# M_J_ext_e_ink_disp-inv.net
KiCad netlist of a schematic drawn in EAGLE
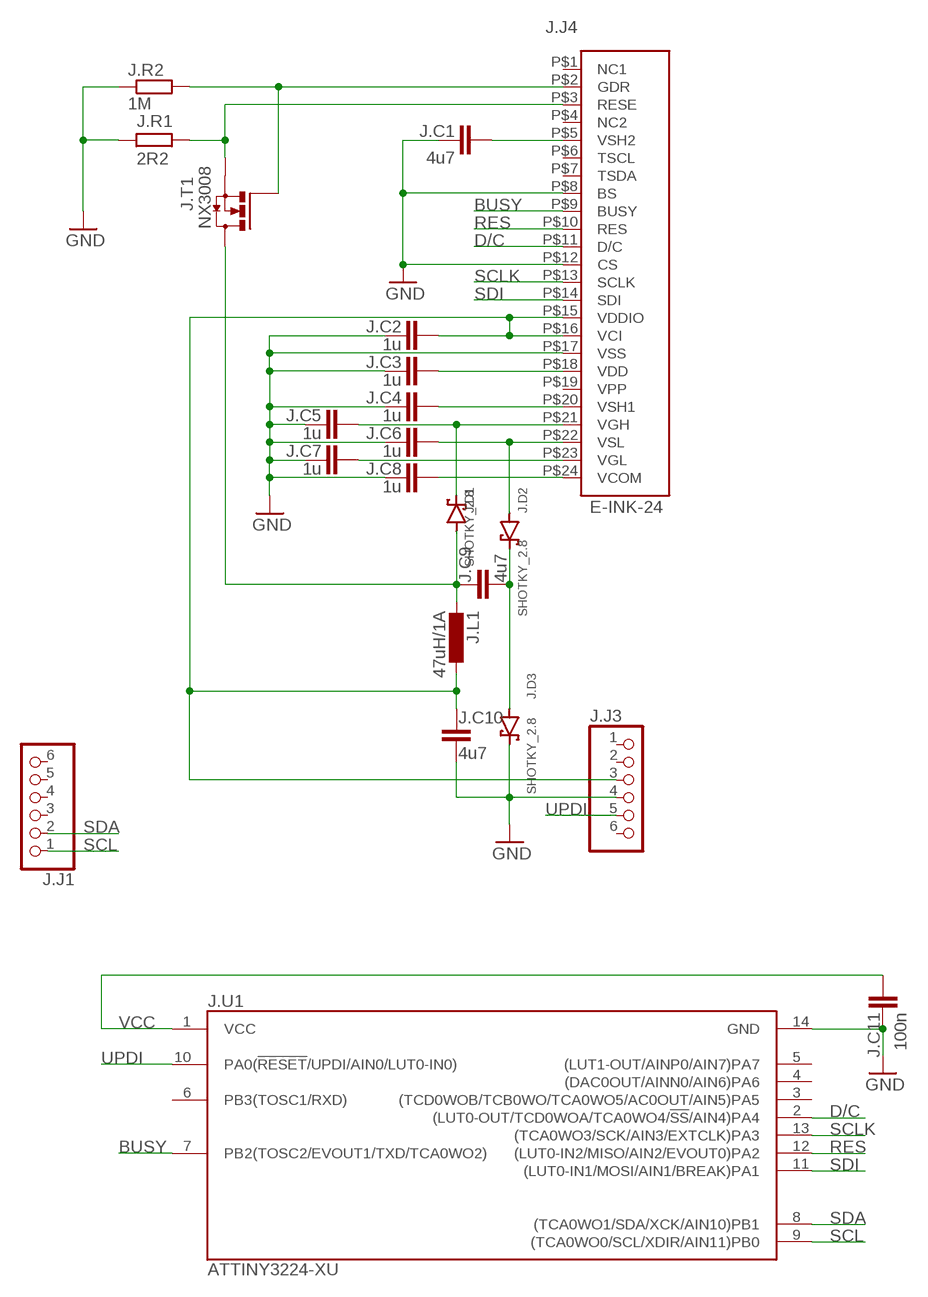
[diagram p0: schematic, sheet 1]

(export (version "E")
  (design (tool "Eeschema 10.0.6"))
  (components
    (comp (ref "J.C1")
      (value "4u7")
      (footprint "eagle-import:C0603")
      (libsource (lib "eagle-import") (part "C-EUC0603"))
    )
    (comp (ref "J.C2")
      (value "1u")
      (footprint "eagle-import:C0603")
      (libsource (lib "eagle-import") (part "C-EUC0603"))
    )
    (comp (ref "J.C3")
      (value "1u")
      (footprint "eagle-import:C0603")
      (libsource (lib "eagle-import") (part "C-EUC0603"))
    )
    (comp (ref "J.C4")
      (value "1u")
      (footprint "eagle-import:C0603")
      (libsource (lib "eagle-import") (part "C-EUC0603"))
    )
    (comp (ref "J.C5")
      (value "1u")
      (footprint "eagle-import:C0603")
      (libsource (lib "eagle-import") (part "C-EUC0603"))
    )
    (comp (ref "J.C6")
      (value "1u")
      (footprint "eagle-import:C0603")
      (libsource (lib "eagle-import") (part "C-EUC0603"))
    )
    (comp (ref "J.C7")
      (value "1u")
      (footprint "eagle-import:C0603")
      (libsource (lib "eagle-import") (part "C-EUC0603"))
    )
    (comp (ref "J.C8")
      (value "1u")
      (footprint "eagle-import:C0603")
      (libsource (lib "eagle-import") (part "C-EUC0603"))
    )
    (comp (ref "J.C9")
      (value "4u7")
      (footprint "eagle-import:C0603")
      (libsource (lib "eagle-import") (part "C-EUC0603"))
    )
    (comp (ref "J.C10")
      (value "4u7")
      (footprint "eagle-import:C0603")
      (libsource (lib "eagle-import") (part "C-EUC0603"))
    )
    (comp (ref "J.C11")
      (value "100n")
      (footprint "eagle-import:C0603")
      (libsource (lib "eagle-import") (part "C-EUC0603"))
    )
    (comp (ref "J.D1")
      (value "SHOTKY_2.8")
      (footprint "eagle-import:SHOTKY_2.8")
      (libsource (lib "eagle-import") (part "SHOTKY_2.8"))
    )
    (comp (ref "J.D2")
      (value "SHOTKY_2.8")
      (footprint "eagle-import:SHOTKY_2.8")
      (libsource (lib "eagle-import") (part "SHOTKY_2.8"))
    )
    (comp (ref "J.D3")
      (value "SHOTKY_2.8")
      (footprint "eagle-import:SHOTKY_2.8")
      (libsource (lib "eagle-import") (part "SHOTKY_2.8"))
    )
    (comp (ref "J.J1")
      (value "PINHD-1X6")
      (footprint "eagle-import:1X06")
      (libsource (lib "eagle-import") (part "PINHD-1X6"))
    )
    (comp (ref "J.J3")
      (value "PINHD-1X6")
      (footprint "eagle-import:1X06")
      (libsource (lib "eagle-import") (part "PINHD-1X6"))
    )
    (comp (ref "J.J4")
      (value "E-INK-24")
      (footprint "eagle-import:E-INK-24")
      (libsource (lib "eagle-import") (part "E-INK-24"))
    )
    (comp (ref "J.L1")
      (value "47uH/1A")
      (footprint "eagle-import:L3230M")
      (libsource (lib "eagle-import") (part "L-EUL3230M"))
    )
    (comp (ref "J.R1")
      (value "2R2")
      (footprint "eagle-import:R0603")
      (libsource (lib "eagle-import") (part "resistor_R-EU_R0603"))
    )
    (comp (ref "J.R2")
      (value "1M")
      (footprint "eagle-import:R0603")
      (libsource (lib "eagle-import") (part "R-EU_R0603"))
    )
    (comp (ref "J.T1")
      (value "NX3008")
      (footprint "eagle-import:SO23")
      (libsource (lib "eagle-import") (part "N-MOSFET"))
    )
    (comp (ref "J.U1")
      (value "ATTINY3224-XU")
      (footprint "eagle-import:TSSOP14")
      (libsource (lib "eagle-import") (part "ATTINY3224-XU"))
    )
  )
  (nets
    (net (code "1") (name "/BUSY") (class "Default")
      (node (ref "J.J4") (pin "P$9") (pinfunction "BUSY_P$9") (pintype "bidirectional"))
      (node (ref "J.U1") (pin "7") (pinfunction "PB2(TOSC2/EVOUT1/TXD/TCA0WO2)_7") (pintype "bidirectional"))
    )
    (net (code "2") (name "/D{slash}C") (class "Default")
      (node (ref "J.J4") (pin "P$11") (pinfunction "D/C_P$11") (pintype "bidirectional"))
      (node (ref "J.U1") (pin "2") (pinfunction "(LUT0-OUT/TCD0WOA/TCA0WO4/~{SS}/AIN4)PA4_2") (pintype "bidirectional"))
    )
    (net (code "3") (name "/RES") (class "Default")
      (node (ref "J.J4") (pin "P$10") (pinfunction "RES_P$10") (pintype "bidirectional"))
      (node (ref "J.U1") (pin "12") (pinfunction "(LUT0-IN2/MISO/AIN2/EVOUT0)PA2_12") (pintype "bidirectional"))
    )
    (net (code "4") (name "/SCL") (class "Default")
      (node (ref "J.J1") (pin "1") (pinfunction "1_1") (pintype "passive"))
      (node (ref "J.U1") (pin "9") (pinfunction "(TCA0WO0/SCL/XDIR/AIN11)PB0_9") (pintype "bidirectional"))
    )
    (net (code "5") (name "/SCLK") (class "Default")
      (node (ref "J.J4") (pin "P$13") (pinfunction "SCLK_P$13") (pintype "bidirectional"))
      (node (ref "J.U1") (pin "13") (pinfunction "(TCA0WO3/SCK/AIN3/EXTCLK)PA3_13") (pintype "bidirectional"))
    )
    (net (code "6") (name "/SDA") (class "Default")
      (node (ref "J.J1") (pin "2") (pinfunction "2_2") (pintype "passive"))
      (node (ref "J.U1") (pin "8") (pinfunction "(TCA0WO1/SDA/XCK/AIN10)PB1_8") (pintype "bidirectional"))
    )
    (net (code "7") (name "/SDI") (class "Default")
      (node (ref "J.J4") (pin "P$14") (pinfunction "SDI_P$14") (pintype "bidirectional"))
      (node (ref "J.U1") (pin "11") (pinfunction "(LUT0-IN1/MOSI/AIN1/BREAK)PA1_11") (pintype "bidirectional"))
    )
    (net (code "8") (name "/UPDI") (class "Default")
      (node (ref "J.J3") (pin "5") (pinfunction "5_5") (pintype "passive"))
      (node (ref "J.U1") (pin "10") (pinfunction "PA0(~{RESET}/UPDI/AIN0/LUT0-IN0)_10") (pintype "bidirectional"))
    )
    (net (code "9") (name "/VCC") (class "Default")
      (node (ref "J.C10") (pin "1") (pinfunction "1_1") (pintype "passive"))
      (node (ref "J.C11") (pin "1") (pinfunction "1_1") (pintype "passive"))
      (node (ref "J.C2") (pin "1") (pinfunction "1_1") (pintype "passive"))
      (node (ref "J.J3") (pin "3") (pinfunction "3_3") (pintype "passive"))
      (node (ref "J.J4") (pin "P$15") (pinfunction "VDDIO_P$15") (pintype "bidirectional"))
      (node (ref "J.J4") (pin "P$16") (pinfunction "VCI_P$16") (pintype "bidirectional"))
      (node (ref "J.L1") (pin "1") (pinfunction "1_1") (pintype "passive"))
      (node (ref "J.U1") (pin "1") (pinfunction "VCC_1") (pintype "bidirectional"))
    )
    (net (code "10") (name "GND") (class "Default")
      (node (ref "J.C1") (pin "2") (pinfunction "2_2") (pintype "passive"))
      (node (ref "J.C10") (pin "2") (pinfunction "2_2") (pintype "passive"))
      (node (ref "J.C11") (pin "2") (pinfunction "2_2") (pintype "passive"))
      (node (ref "J.C2") (pin "2") (pinfunction "2_2") (pintype "passive"))
      (node (ref "J.C3") (pin "2") (pinfunction "2_2") (pintype "passive"))
      (node (ref "J.C4") (pin "2") (pinfunction "2_2") (pintype "passive"))
      (node (ref "J.C5") (pin "2") (pinfunction "2_2") (pintype "passive"))
      (node (ref "J.C6") (pin "2") (pinfunction "2_2") (pintype "passive"))
      (node (ref "J.C7") (pin "2") (pinfunction "2_2") (pintype "passive"))
      (node (ref "J.C8") (pin "2") (pinfunction "2_2") (pintype "passive"))
      (node (ref "J.D3") (pin "K") (pinfunction "C_K") (pintype "passive"))
      (node (ref "J.J3") (pin "4") (pinfunction "4_4") (pintype "passive"))
      (node (ref "J.J4") (pin "P$12") (pinfunction "CS_P$12") (pintype "bidirectional"))
      (node (ref "J.J4") (pin "P$17") (pinfunction "VSS_P$17") (pintype "bidirectional"))
      (node (ref "J.J4") (pin "P$8") (pinfunction "BS_P$8") (pintype "bidirectional"))
      (node (ref "J.R1") (pin "2") (pinfunction "2_2") (pintype "passive"))
      (node (ref "J.R2") (pin "1") (pinfunction "1_1") (pintype "passive"))
      (node (ref "J.U1") (pin "14") (pinfunction "GND_14") (pintype "bidirectional"))
    )
    (net (code "11") (name "Net-(J.C9-Pad1)") (class "Default")
      (node (ref "J.C9") (pin "1") (pinfunction "1_1") (pintype "passive"))
      (node (ref "J.D1") (pin "A") (pinfunction "A_A") (pintype "passive"))
      (node (ref "J.L1") (pin "2") (pinfunction "2_2") (pintype "passive"))
      (node (ref "J.T1") (pin "D") (pinfunction "D_D") (pintype "passive"))
    )
    (net (code "12") (name "Net-(J.D1-C)") (class "Default")
      (node (ref "J.C5") (pin "1") (pinfunction "1_1") (pintype "passive"))
      (node (ref "J.D1") (pin "K") (pinfunction "C_K") (pintype "passive"))
      (node (ref "J.J4") (pin "P$21") (pinfunction "VGH_P$21") (pintype "bidirectional"))
    )
    (net (code "13") (name "Net-(J.D2-C)") (class "Default")
      (node (ref "J.C9") (pin "2") (pinfunction "2_2") (pintype "passive"))
      (node (ref "J.D2") (pin "K") (pinfunction "C_K") (pintype "passive"))
      (node (ref "J.D3") (pin "A") (pinfunction "A_A") (pintype "passive"))
    )
    (net (code "14") (name "Net-(J.J4-GDR)") (class "Default")
      (node (ref "J.J4") (pin "P$2") (pinfunction "GDR_P$2") (pintype "bidirectional"))
      (node (ref "J.R2") (pin "2") (pinfunction "2_2") (pintype "passive"))
      (node (ref "J.T1") (pin "G") (pinfunction "G_G") (pintype "passive"))
    )
    (net (code "15") (name "Net-(J.J4-RESE)") (class "Default")
      (node (ref "J.J4") (pin "P$3") (pinfunction "RESE_P$3") (pintype "bidirectional"))
      (node (ref "J.R1") (pin "1") (pinfunction "1_1") (pintype "passive"))
      (node (ref "J.T1") (pin "S") (pinfunction "S_S") (pintype "passive"))
    )
    (net (code "16") (name "Net-(J.J4-VCOM)") (class "Default")
      (node (ref "J.C8") (pin "1") (pinfunction "1_1") (pintype "passive"))
      (node (ref "J.J4") (pin "P$24") (pinfunction "VCOM_P$24") (pintype "bidirectional"))
    )
    (net (code "17") (name "Net-(J.J4-VDD)") (class "Default")
      (node (ref "J.C3") (pin "1") (pinfunction "1_1") (pintype "passive"))
      (node (ref "J.J4") (pin "P$18") (pinfunction "VDD_P$18") (pintype "bidirectional"))
    )
    (net (code "18") (name "Net-(J.J4-VGL)") (class "Default")
      (node (ref "J.C7") (pin "1") (pinfunction "1_1") (pintype "passive"))
      (node (ref "J.J4") (pin "P$23") (pinfunction "VGL_P$23") (pintype "bidirectional"))
    )
    (net (code "19") (name "Net-(J.J4-VSH1)") (class "Default")
      (node (ref "J.C4") (pin "1") (pinfunction "1_1") (pintype "passive"))
      (node (ref "J.J4") (pin "P$20") (pinfunction "VSH1_P$20") (pintype "bidirectional"))
    )
    (net (code "20") (name "Net-(J.J4-VSH2)") (class "Default")
      (node (ref "J.C1") (pin "1") (pinfunction "1_1") (pintype "passive"))
      (node (ref "J.J4") (pin "P$5") (pinfunction "VSH2_P$5") (pintype "bidirectional"))
    )
    (net (code "21") (name "Net-(J.J4-VSL)") (class "Default")
      (node (ref "J.C6") (pin "1") (pinfunction "1_1") (pintype "passive"))
      (node (ref "J.D2") (pin "A") (pinfunction "A_A") (pintype "passive"))
      (node (ref "J.J4") (pin "P$22") (pinfunction "VSL_P$22") (pintype "bidirectional"))
    )
    (net (code "22") (name "unconnected-(J.J1-Pad3)") (class "Default")
      (node (ref "J.J1") (pin "3") (pinfunction "3_3") (pintype "passive"))
    )
    (net (code "23") (name "unconnected-(J.J1-Pad4)") (class "Default")
      (node (ref "J.J1") (pin "4") (pinfunction "4_4") (pintype "passive"))
    )
    (net (code "24") (name "unconnected-(J.J1-Pad5)") (class "Default")
      (node (ref "J.J1") (pin "5") (pinfunction "5_5") (pintype "passive"))
    )
    (net (code "25") (name "unconnected-(J.J1-Pad6)") (class "Default")
      (node (ref "J.J1") (pin "6") (pinfunction "6_6") (pintype "passive"))
    )
    (net (code "26") (name "unconnected-(J.J3-Pad1)") (class "Default")
      (node (ref "J.J3") (pin "1") (pinfunction "1_1") (pintype "passive"))
    )
    (net (code "27") (name "unconnected-(J.J3-Pad2)") (class "Default")
      (node (ref "J.J3") (pin "2") (pinfunction "2_2") (pintype "passive"))
    )
    (net (code "28") (name "unconnected-(J.J3-Pad6)") (class "Default")
      (node (ref "J.J3") (pin "6") (pinfunction "6_6") (pintype "passive"))
    )
    (net (code "29") (name "unconnected-(J.J4-NC1-PadP$1)") (class "Default")
      (node (ref "J.J4") (pin "P$1") (pinfunction "NC1_P$1") (pintype "bidirectional"))
    )
    (net (code "30") (name "unconnected-(J.J4-NC2-PadP$4)") (class "Default")
      (node (ref "J.J4") (pin "P$4") (pinfunction "NC2_P$4") (pintype "bidirectional"))
    )
    (net (code "31") (name "unconnected-(J.J4-TSCL-PadP$6)") (class "Default")
      (node (ref "J.J4") (pin "P$6") (pinfunction "TSCL_P$6") (pintype "bidirectional"))
    )
    (net (code "32") (name "unconnected-(J.J4-TSDA-PadP$7)") (class "Default")
      (node (ref "J.J4") (pin "P$7") (pinfunction "TSDA_P$7") (pintype "bidirectional"))
    )
    (net (code "33") (name "unconnected-(J.J4-VPP-PadP$19)") (class "Default")
      (node (ref "J.J4") (pin "P$19") (pinfunction "VPP_P$19") (pintype "bidirectional"))
    )
    (net (code "34") (name "unconnected-(J.U1-(DAC0OUT{slash}AINN0{slash}AIN6)PA6-Pad4)") (class "Default")
      (node (ref "J.U1") (pin "4") (pinfunction "(DAC0OUT/AINN0/AIN6)PA6_4") (pintype "bidirectional"))
    )
    (net (code "35") (name "unconnected-(J.U1-(LUT1-OUT{slash}AINP0{slash}AIN7)PA7-Pad5)") (class "Default")
      (node (ref "J.U1") (pin "5") (pinfunction "(LUT1-OUT/AINP0/AIN7)PA7_5") (pintype "bidirectional"))
    )
    (net (code "36") (name "unconnected-(J.U1-(TCD0WOB{slash}TCB0WO{slash}TCA0WO5{slash}AC0OUT{slash}AIN5)PA5-Pad3)") (class "Default")
      (node (ref "J.U1") (pin "3") (pinfunction "(TCD0WOB/TCB0WO/TCA0WO5/AC0OUT/AIN5)PA5_3") (pintype "bidirectional"))
    )
    (net (code "37") (name "unconnected-(J.U1-PB3(TOSC1{slash}RXD)-Pad6)") (class "Default")
      (node (ref "J.U1") (pin "6") (pinfunction "PB3(TOSC1/RXD)_6") (pintype "bidirectional"))
    )
  )
)
